# LD.net
KiCad netlist of a schematic drawn in Altium Designer
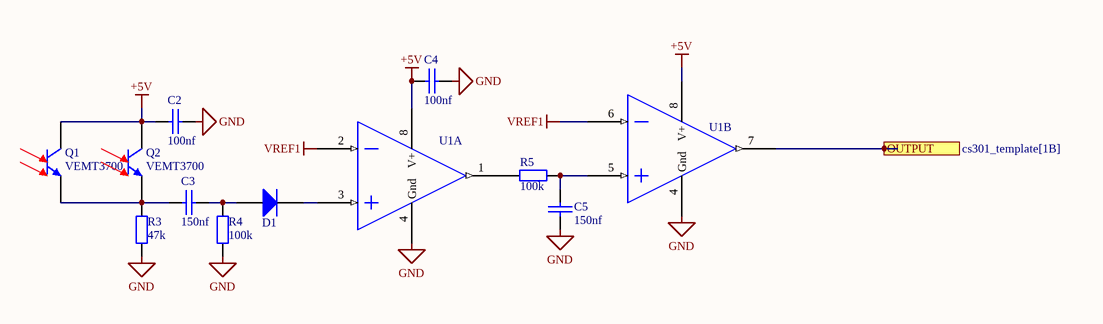
[diagram p0: LD.SchDoc]

(export (version "E")
  (design (tool "Eeschema 10.0.6"))
  (components
    (comp (ref "C2")
      (value "100nf")
      (footprint "0805 CAP")
      (description "SMT ceramic capacitor 0805 size")
      (libsource (lib "COMSYS301_2025") (part "CerCap_SMT_0805"))
    )
    (comp (ref "C3")
      (value "150nf")
      (footprint "0805 CAP")
      (description "SMT ceramic capacitor 0805 size")
      (libsource (lib "COMSYS301_2025") (part "CerCap_SMT_0805"))
    )
    (comp (ref "C4")
      (value "100nf")
      (footprint "0805 CAP")
      (description "SMT ceramic capacitor 0805 size")
      (libsource (lib "COMSYS301_2025") (part "CerCap_SMT_0805"))
    )
    (comp (ref "C5")
      (value "150nf")
      (footprint "0805 CAP")
      (description "SMT ceramic capacitor 0805 size")
      (libsource (lib "COMSYS301_2025") (part "CerCap_SMT_0805"))
    )
    (comp (ref "D1")
      (value "~")
      (footprint "ECE-DIO10.46-5.3x2.8TH")
      (description "Schottky Small Signal Diode 200mA 30V TH")
      (libsource (lib "EceParts") (part "Diode"))
    )
    (comp (ref "Q1")
      (value "VEMT3700")
      (footprint "0805 LED")
      (description "Silicon NPN Phototransistor")
      (libsource (lib "COMSYS301_2025") (part "VEMT3700"))
    )
    (comp (ref "Q2")
      (value "VEMT3700")
      (footprint "0805 LED")
      (description "Silicon NPN Phototransistor")
      (libsource (lib "COMSYS301_2025") (part "VEMT3700"))
    )
    (comp (ref "R3")
      (value "47k")
      (footprint "0805 RES")
      (description "0805 resistor")
      (fields (field (name "PUBLISHER") "Altium Limited"))
      (libsource (lib "COMSYS301_2025") (part "Res_SMT_0805"))
    )
    (comp (ref "R4")
      (value "100k")
      (footprint "0805 RES")
      (description "0805 resistor")
      (fields (field (name "PUBLISHER") "Altium Limited"))
      (libsource (lib "COMSYS301_2025") (part "Res_SMT_0805"))
    )
    (comp (ref "R5")
      (value "100k")
      (footprint "0805 RES")
      (description "0805 resistor")
      (fields (field (name "PUBLISHER") "Altium Limited"))
      (libsource (lib "") (part "Res_SMT_0805_1"))
    )
    (comp (ref "U1")
      (value "TLC082")
      (footprint "ECE-SOIC8")
      (description "IC OPAMP TLC082 GP 10MHZ 8SOIC")
      (libsource (lib "EceParts") (part "TLC082"))
    )
  )
  (nets
    (net (code "1") (name "+5V") (class "Default")
      (node (ref "C2") (pin "1") (pinfunction "1_1") (pintype "passive"))
      (node (ref "C4") (pin "1") (pinfunction "1_1") (pintype "passive"))
      (node (ref "Q1") (pin "1") (pinfunction "C_1") (pintype "passive"))
      (node (ref "Q2") (pin "1") (pinfunction "C_1") (pintype "passive"))
      (node (ref "U1") (pin "8") (pinfunction "V+_8") (pintype "power_in"))
    )
    (net (code "2") (name "/OUTPUT") (class "Default")
      (node (ref "U1") (pin "7") (pinfunction "OUT2_7") (pintype "output"))
    )
    (net (code "3") (name "GND") (class "Default")
      (node (ref "C2") (pin "2") (pinfunction "2_2") (pintype "passive"))
      (node (ref "C4") (pin "2") (pinfunction "2_2") (pintype "passive"))
      (node (ref "C5") (pin "2") (pinfunction "2_2") (pintype "passive"))
      (node (ref "R3") (pin "1") (pinfunction "1_1") (pintype "passive"))
      (node (ref "R4") (pin "1") (pinfunction "1_1") (pintype "passive"))
      (node (ref "U1") (pin "4") (pinfunction "Gnd_4") (pintype "power_in"))
    )
    (net (code "4") (name "Net-(D1-A)") (class "Default")
      (node (ref "C3") (pin "2") (pinfunction "2_2") (pintype "passive"))
      (node (ref "D1") (pin "1") (pinfunction "A_1") (pintype "passive"))
      (node (ref "R4") (pin "2") (pinfunction "2_2") (pintype "passive"))
    )
    (net (code "5") (name "Net-(D1-K)") (class "Default")
      (node (ref "D1") (pin "2") (pinfunction "K_2") (pintype "passive"))
      (node (ref "U1") (pin "3") (pinfunction "IN1(+)_3") (pintype "input"))
    )
    (net (code "6") (name "Net-(Q1-E)") (class "Default")
      (node (ref "C3") (pin "1") (pinfunction "1_1") (pintype "passive"))
      (node (ref "Q1") (pin "2") (pinfunction "E_2") (pintype "passive"))
      (node (ref "Q2") (pin "2") (pinfunction "E_2") (pintype "passive"))
      (node (ref "R3") (pin "2") (pinfunction "2_2") (pintype "passive"))
    )
    (net (code "7") (name "Net-(U1A-OUT1)") (class "Default")
      (node (ref "R5") (pin "1") (pinfunction "1_1") (pintype "passive"))
      (node (ref "U1") (pin "1") (pinfunction "OUT1_1") (pintype "output"))
    )
    (net (code "8") (name "Net-(U1B-IN2(+))") (class "Default")
      (node (ref "C5") (pin "1") (pinfunction "1_1") (pintype "passive"))
      (node (ref "R5") (pin "2") (pinfunction "2_2") (pintype "passive"))
      (node (ref "U1") (pin "5") (pinfunction "IN2(+)_5") (pintype "input"))
    )
    (net (code "9") (name "VREF1") (class "Default")
      (node (ref "U1") (pin "2") (pinfunction "IN1(-)_2") (pintype "input"))
      (node (ref "U1") (pin "6") (pinfunction "IN2(-)_6") (pintype "input"))
    )
  )
)
